# SchematicDesign.net
KiCad netlist of a schematic drawn in Altium Designer
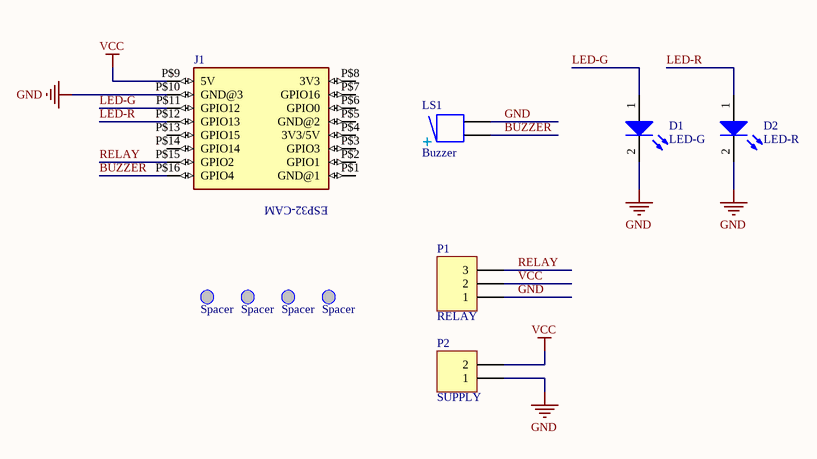
[diagram p0: SchematicDesign.SchDoc]

(export (version "E")
  (design (tool "Eeschema 10.0.6"))
  (components
    (comp (ref "1")
      (value "Spacer")
      (footprint "Spacer")
      (fields (field (name "PUBLISHER") "Altium Limited"))
      (libsource (lib "Custom") (part "Spacer"))
    )
    (comp (ref "2")
      (value "Spacer")
      (footprint "Spacer")
      (fields (field (name "PUBLISHER") "Altium Limited"))
      (libsource (lib "Custom") (part "Spacer"))
    )
    (comp (ref "3")
      (value "Spacer")
      (footprint "Spacer")
      (fields (field (name "PUBLISHER") "Altium Limited"))
      (libsource (lib "Custom") (part "Spacer"))
    )
    (comp (ref "4")
      (value "Spacer")
      (footprint "Spacer")
      (fields (field (name "PUBLISHER") "Altium Limited"))
      (libsource (lib "Custom") (part "Spacer"))
    )
    (comp (ref "D1")
      (value "LED-G")
      (footprint "LED")
      (description "LED 3mm or 5mm")
      (fields (field (name "PUBLISHER") "Altium Limited"))
      (libsource (lib "UKK 2018") (part "LED"))
    )
    (comp (ref "D2")
      (value "LED-R")
      (footprint "LED")
      (description "LED 3mm or 5mm")
      (fields (field (name "PUBLISHER") "Altium Limited"))
      (libsource (lib "UKK 2018") (part "LED"))
    )
    (comp (ref "J1")
      (value "ESP32-CAM")
      (footprint "ESP32-CAM")
      (fields (field (name "MF") "AI-Thinker"))
      (libsource (lib "ESP32-CAM") (part "ESP32-CAM"))
    )
    (comp (ref "LS1")
      (value "Buzzer")
      (footprint "BUZZER")
      (description "Magnetic Transducer Buzzer")
      (fields (field (name "PUBLISHER") "Altium Limited"))
      (libsource (lib "Ahahahahah Old") (part "Buzzer"))
    )
    (comp (ref "P1")
      (value "RELAY")
      (footprint "HDR1X3")
      (description "Header, 3-Pin")
      (fields (field (name "PUBLISHER") "Altium Limited"))
      (libsource (lib "Miscellaneous Connectors") (part "Header 3"))
    )
    (comp (ref "P2")
      (value "SUPPLY")
      (footprint "Term.Block 2pin")
      (description "Terminal Block, 2-Pin")
      (fields (field (name "PUBLISHER") "Altium Limited"))
      (libsource (lib "Custom") (part "Terminal Block 2pin"))
    )
  )
  (nets
    (net (code "1") (name "/BUZZER") (class "Default")
      (node (ref "J1") (pin "P$16") (pinfunction "GPIO4_P$16") (pintype "bidirectional"))
      (node (ref "LS1") (pin "1") (pinfunction "1_1") (pintype "passive"))
    )
    (net (code "2") (name "/LED-G") (class "Default")
      (node (ref "D1") (pin "1") (pinfunction "A_1") (pintype "passive"))
      (node (ref "J1") (pin "P$11") (pinfunction "GPIO12_P$11") (pintype "bidirectional"))
    )
    (net (code "3") (name "/LED-R") (class "Default")
      (node (ref "D2") (pin "1") (pinfunction "A_1") (pintype "passive"))
      (node (ref "J1") (pin "P$12") (pinfunction "GPIO13_P$12") (pintype "bidirectional"))
    )
    (net (code "4") (name "/RELAY") (class "Default")
      (node (ref "J1") (pin "P$15") (pinfunction "GPIO2_P$15") (pintype "bidirectional"))
      (node (ref "P1") (pin "3") (pinfunction "3_3") (pintype "passive"))
    )
    (net (code "5") (name "GND") (class "Default")
      (node (ref "D1") (pin "2") (pinfunction "K_2") (pintype "passive"))
      (node (ref "D2") (pin "2") (pinfunction "K_2") (pintype "passive"))
      (node (ref "J1") (pin "P$10") (pinfunction "GND@3_P$10") (pintype "bidirectional"))
      (node (ref "LS1") (pin "2") (pinfunction "2_2") (pintype "passive"))
      (node (ref "P1") (pin "1") (pinfunction "1_1") (pintype "passive"))
      (node (ref "P2") (pin "0") (pinfunction "1_0") (pintype "passive"))
    )
    (net (code "6") (name "VCC") (class "Default")
      (node (ref "J1") (pin "P$9") (pinfunction "5V_P$9") (pintype "bidirectional"))
      (node (ref "P1") (pin "2") (pinfunction "2_2") (pintype "passive"))
      (node (ref "P2") (pin "1") (pinfunction "2_1") (pintype "passive"))
    )
    (net (code "7") (name "unconnected-(J1-3V3-PadP$8)") (class "Default")
      (node (ref "J1") (pin "P$8") (pinfunction "3V3_P$8") (pintype "bidirectional"))
    )
    (net (code "8") (name "unconnected-(J1-3V3{slash}5V-PadP$4)") (class "Default")
      (node (ref "J1") (pin "P$4") (pinfunction "3V3/5V_P$4") (pintype "bidirectional"))
    )
    (net (code "9") (name "unconnected-(J1-GND@1-PadP$1)") (class "Default")
      (node (ref "J1") (pin "P$1") (pinfunction "GND@1_P$1") (pintype "bidirectional"))
    )
    (net (code "10") (name "unconnected-(J1-GND@2-PadP$5)") (class "Default")
      (node (ref "J1") (pin "P$5") (pinfunction "GND@2_P$5") (pintype "bidirectional"))
    )
    (net (code "11") (name "unconnected-(J1-GPIO0-PadP$6)") (class "Default")
      (node (ref "J1") (pin "P$6") (pinfunction "GPIO0_P$6") (pintype "bidirectional"))
    )
    (net (code "12") (name "unconnected-(J1-GPIO1-PadP$2)") (class "Default")
      (node (ref "J1") (pin "P$2") (pinfunction "GPIO1_P$2") (pintype "bidirectional"))
    )
    (net (code "13") (name "unconnected-(J1-GPIO3-PadP$3)") (class "Default")
      (node (ref "J1") (pin "P$3") (pinfunction "GPIO3_P$3") (pintype "bidirectional"))
    )
    (net (code "14") (name "unconnected-(J1-GPIO14-PadP$14)") (class "Default")
      (node (ref "J1") (pin "P$14") (pinfunction "GPIO14_P$14") (pintype "bidirectional"))
    )
    (net (code "15") (name "unconnected-(J1-GPIO15-PadP$13)") (class "Default")
      (node (ref "J1") (pin "P$13") (pinfunction "GPIO15_P$13") (pintype "bidirectional"))
    )
    (net (code "16") (name "unconnected-(J1-GPIO16-PadP$7)") (class "Default")
      (node (ref "J1") (pin "P$7") (pinfunction "GPIO16_P$7") (pintype "bidirectional"))
    )
  )
)
